# sensor_pcb_4.net
KiCad netlist of a schematic drawn in EAGLE
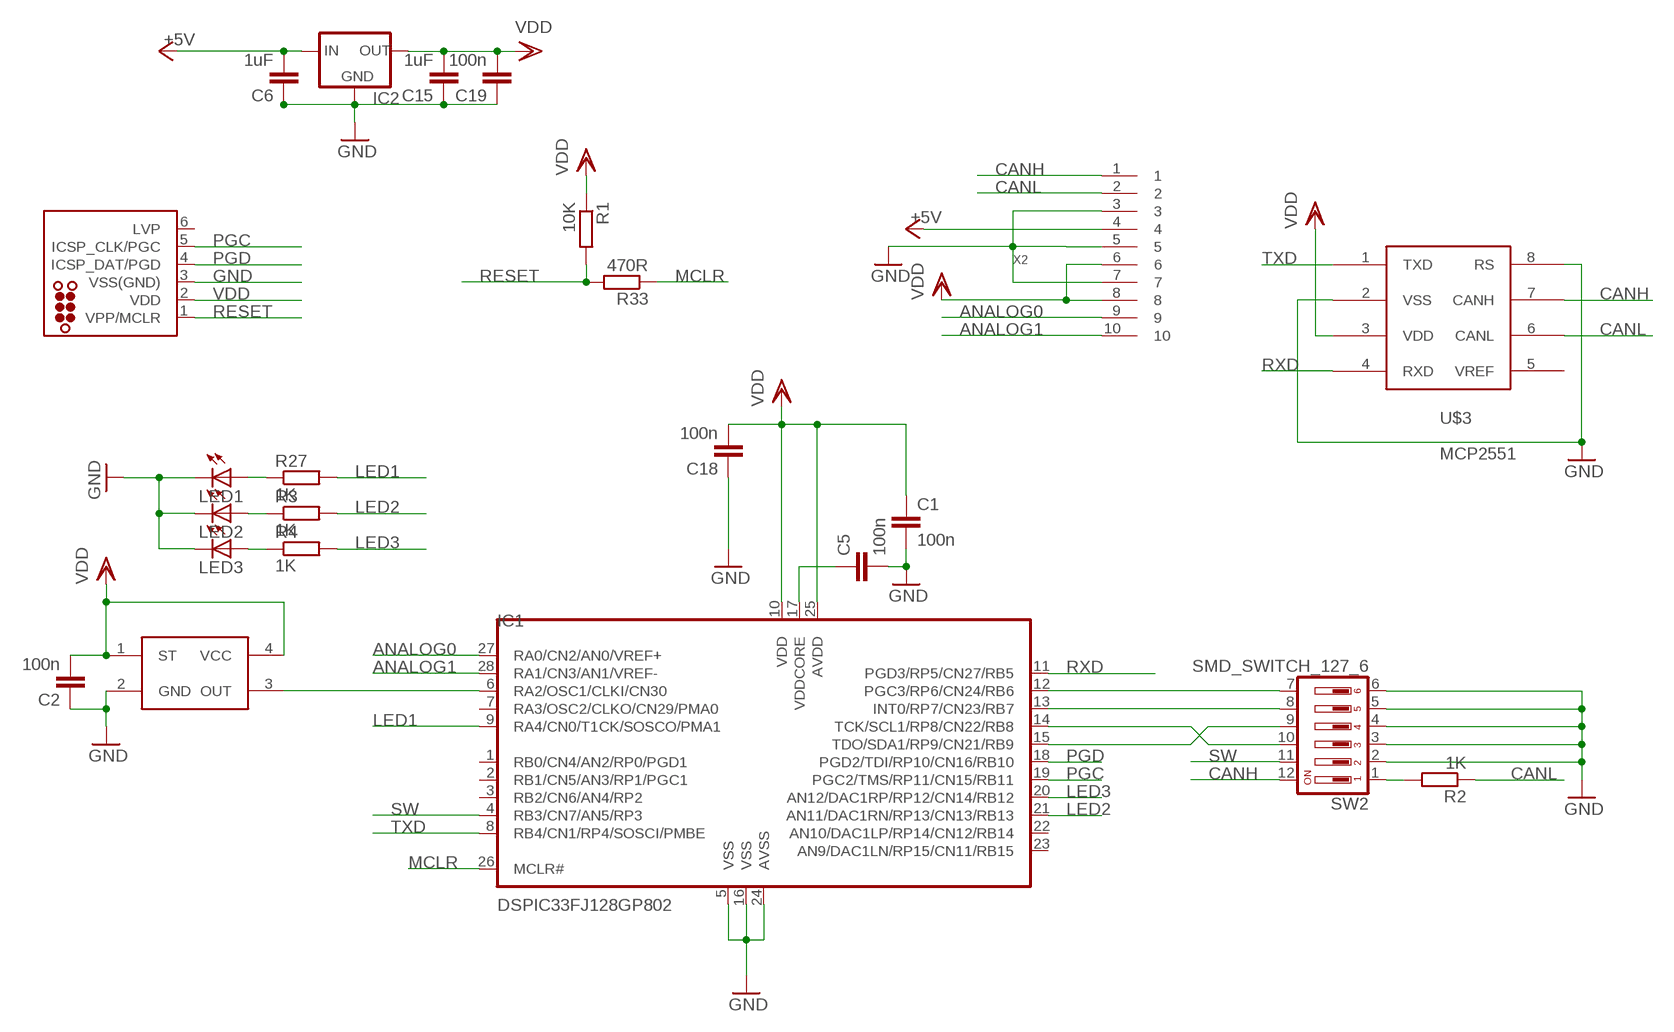
[diagram p0: schematic, sheet 1]

(export (version "E")
  (design (tool "Eeschema 10.0.6"))
  (components
    (comp (ref "C1")
      (value "100n")
      (footprint "eagle-import:C0402K")
      (libsource (lib "eagle-import") (part "C-EUC0402K"))
    )
    (comp (ref "C2")
      (value "100n")
      (footprint "eagle-import:C0402K")
      (libsource (lib "eagle-import") (part "C-EUC0402K"))
    )
    (comp (ref "C5")
      (value "100n")
      (footprint "eagle-import:C0402K")
      (libsource (lib "eagle-import") (part "C-EUC0402K"))
    )
    (comp (ref "C6")
      (value "1uF")
      (footprint "eagle-import:C0402K")
      (libsource (lib "eagle-import") (part "C-EUC0402K"))
    )
    (comp (ref "C15")
      (value "1uF")
      (footprint "eagle-import:C0402K")
      (libsource (lib "eagle-import") (part "C-EUC0402K"))
    )
    (comp (ref "C18")
      (value "100n")
      (footprint "eagle-import:C0402K")
      (libsource (lib "eagle-import") (part "C-EUC0402K"))
    )
    (comp (ref "C19")
      (value "100n")
      (footprint "eagle-import:C0402K")
      (libsource (lib "eagle-import") (part "C-EUC0402K"))
    )
    (comp (ref "IC1")
      (value "DSPIC33FJ128GP802")
      (footprint "eagle-import:QFN-S28-6X6")
      (libsource (lib "eagle-import") (part "DSPIC33FJ128GP802"))
    )
    (comp (ref "IC2")
      (value "XC63FPM")
      (footprint "eagle-import:SOT23")
      (libsource (lib "eagle-import") (part "XC63FPM"))
    )
    (comp (ref "J1")
      (value "TC2030-MCP-NL")
      (footprint "eagle-import:TC2030-MCP-NL")
      (libsource (lib "eagle-import") (part "TC2030-MCP-NL"))
    )
    (comp (ref "LED1")
      (value "LEDCHIPLED_0603")
      (footprint "eagle-import:CHIPLED_0603")
      (libsource (lib "eagle-import") (part "LEDCHIPLED_0603"))
    )
    (comp (ref "LED2")
      (value "LEDCHIPLED_0603")
      (footprint "eagle-import:CHIPLED_0603")
      (libsource (lib "eagle-import") (part "LEDCHIPLED_0603"))
    )
    (comp (ref "LED3")
      (value "LEDCHIPLED_0603")
      (footprint "eagle-import:CHIPLED_0603")
      (libsource (lib "eagle-import") (part "LEDCHIPLED_0603"))
    )
    (comp (ref "R1")
      (value "10K")
      (footprint "eagle-import:R0402")
      (libsource (lib "eagle-import") (part "R-EU_R0402"))
    )
    (comp (ref "R2")
      (value "1K")
      (footprint "eagle-import:R0402")
      (libsource (lib "eagle-import") (part "R-EU_R0402"))
    )
    (comp (ref "R3")
      (value "1K")
      (footprint "eagle-import:R0402")
      (libsource (lib "eagle-import") (part "R-EU_R0402"))
    )
    (comp (ref "R4")
      (value "1K")
      (footprint "eagle-import:R0402")
      (libsource (lib "eagle-import") (part "R-EU_R0402"))
    )
    (comp (ref "R27")
      (value "1K")
      (footprint "eagle-import:R0402")
      (libsource (lib "eagle-import") (part "R-EU_R0402"))
    )
    (comp (ref "R33")
      (value "470R")
      (footprint "eagle-import:R0402")
      (libsource (lib "eagle-import") (part "R-EU_R0402"))
    )
    (comp (ref "SW2")
      (value "SMD_SWITCH_127_6")
      (footprint "eagle-import:SMD_SWITCH_127_6")
      (libsource (lib "eagle-import") (part "SMD_SWITCH_127_6"))
    )
    (comp (ref "U$1")
      (value "SG-310")
      (footprint "eagle-import:SG-310")
      (libsource (lib "eagle-import") (part "SG-310"))
    )
    (comp (ref "U$3")
      (value "MCP2551")
      (footprint "eagle-import:999")
      (libsource (lib "eagle-import") (part "MCP2551"))
    )
    (comp (ref "X2")
      (value "10PINJAS")
      (footprint "eagle-import:10PIN0.1")
      (libsource (lib "eagle-import") (part "10PINJAS"))
    )
  )
  (nets
    (net (code "1") (name "+5V") (class "Default")
      (node (ref "C6") (pin "2") (pinfunction "2_2") (pintype "passive"))
      (node (ref "IC2") (pin "3") (pinfunction "IN_3") (pintype "input"))
      (node (ref "X2") (pin "4") (pinfunction "4_4") (pintype "bidirectional"))
    )
    (net (code "2") (name "/ANALOG0") (class "Default")
      (node (ref "IC1") (pin "27") (pinfunction "RA0/CN2/AN0/VREF+_27") (pintype "bidirectional"))
      (node (ref "X2") (pin "9") (pinfunction "9_9") (pintype "bidirectional"))
    )
    (net (code "3") (name "/ANALOG1") (class "Default")
      (node (ref "IC1") (pin "28") (pinfunction "RA1/CN3/AN1/VREF-_28") (pintype "bidirectional"))
      (node (ref "X2") (pin "10") (pinfunction "10_10") (pintype "bidirectional"))
    )
    (net (code "4") (name "/CANH") (class "Default")
      (node (ref "SW2") (pin "12") (pinfunction "12_12") (pintype "passive"))
      (node (ref "U$3") (pin "7") (pinfunction "CANH_7") (pintype "bidirectional"))
      (node (ref "X2") (pin "1") (pinfunction "1_1") (pintype "bidirectional"))
    )
    (net (code "5") (name "/CANL") (class "Default")
      (node (ref "R2") (pin "1") (pinfunction "1_1") (pintype "passive"))
      (node (ref "U$3") (pin "6") (pinfunction "CANL_6") (pintype "bidirectional"))
      (node (ref "X2") (pin "2") (pinfunction "2_2") (pintype "bidirectional"))
    )
    (net (code "6") (name "/LED1") (class "Default")
      (node (ref "IC1") (pin "9") (pinfunction "RA4/CN0/T1CK/SOSCO/PMA1_9") (pintype "bidirectional"))
      (node (ref "R27") (pin "2") (pinfunction "2_2") (pintype "passive"))
    )
    (net (code "7") (name "/LED2") (class "Default")
      (node (ref "IC1") (pin "21") (pinfunction "AN11/DAC1RN/RP13/CN13/RB13_21") (pintype "bidirectional"))
      (node (ref "R3") (pin "2") (pinfunction "2_2") (pintype "passive"))
    )
    (net (code "8") (name "/LED3") (class "Default")
      (node (ref "IC1") (pin "20") (pinfunction "AN12/DAC1RP/RP12/CN14/RB12_20") (pintype "bidirectional"))
      (node (ref "R4") (pin "2") (pinfunction "2_2") (pintype "passive"))
    )
    (net (code "9") (name "/MCLR") (class "Default")
      (node (ref "IC1") (pin "26") (pinfunction "MCLR#_26") (pintype "input"))
      (node (ref "R33") (pin "1") (pinfunction "1_1") (pintype "passive"))
    )
    (net (code "10") (name "/PGC") (class "Default")
      (node (ref "IC1") (pin "19") (pinfunction "PGC2/TMS/RP11/CN15/RB11_19") (pintype "bidirectional"))
      (node (ref "J1") (pin "5") (pinfunction "ICSP_CLK/PGC_5") (pintype "output"))
    )
    (net (code "11") (name "/PGD") (class "Default")
      (node (ref "IC1") (pin "18") (pinfunction "PGD2/TDI/RP10/CN16/RB10_18") (pintype "bidirectional"))
      (node (ref "J1") (pin "4") (pinfunction "ICSP_DAT/PGD_4") (pintype "bidirectional"))
    )
    (net (code "12") (name "/RESET") (class "Default")
      (node (ref "J1") (pin "1") (pinfunction "VPP/MCLR_1") (pintype "passive"))
      (node (ref "R1") (pin "2") (pinfunction "2_2") (pintype "passive"))
      (node (ref "R33") (pin "2") (pinfunction "2_2") (pintype "passive"))
    )
    (net (code "13") (name "/RXD") (class "Default")
      (node (ref "IC1") (pin "11") (pinfunction "PGD3/RP5/CN27/RB5_11") (pintype "bidirectional"))
      (node (ref "U$3") (pin "4") (pinfunction "RXD_4") (pintype "bidirectional"))
    )
    (net (code "14") (name "/SW") (class "Default")
      (node (ref "IC1") (pin "4") (pinfunction "RB3/CN7/AN5/RP3_4") (pintype "bidirectional"))
      (node (ref "SW2") (pin "11") (pinfunction "11_11") (pintype "passive"))
    )
    (net (code "15") (name "/TXD") (class "Default")
      (node (ref "IC1") (pin "8") (pinfunction "RB4/CN1/RP4/SOSCI/PMBE_8") (pintype "bidirectional"))
      (node (ref "U$3") (pin "1") (pinfunction "TXD_1") (pintype "bidirectional"))
    )
    (net (code "16") (name "GND") (class "Default")
      (node (ref "C1") (pin "2") (pinfunction "2_2") (pintype "passive"))
      (node (ref "C15") (pin "1") (pinfunction "1_1") (pintype "passive"))
      (node (ref "C18") (pin "1") (pinfunction "1_1") (pintype "passive"))
      (node (ref "C19") (pin "1") (pinfunction "1_1") (pintype "passive"))
      (node (ref "C2") (pin "1") (pinfunction "1_1") (pintype "passive"))
      (node (ref "C5") (pin "2") (pinfunction "2_2") (pintype "passive"))
      (node (ref "C6") (pin "1") (pinfunction "1_1") (pintype "passive"))
      (node (ref "IC1") (pin "16") (pinfunction "VSS_16") (pintype "power_in"))
      (node (ref "IC1") (pin "24") (pinfunction "AVSS_24") (pintype "power_in"))
      (node (ref "IC1") (pin "5") (pinfunction "VSS_5") (pintype "power_in"))
      (node (ref "IC2") (pin "1") (pinfunction "GND_1") (pintype "input"))
      (node (ref "J1") (pin "3") (pinfunction "VSS(GND)_3") (pintype "power_in"))
      (node (ref "LED1") (pin "C") (pinfunction "C_C") (pintype "passive"))
      (node (ref "LED2") (pin "C") (pinfunction "C_C") (pintype "passive"))
      (node (ref "LED3") (pin "C") (pinfunction "C_C") (pintype "passive"))
      (node (ref "SW2") (pin "2") (pinfunction "2_2") (pintype "passive"))
      (node (ref "SW2") (pin "3") (pinfunction "3_3") (pintype "passive"))
      (node (ref "SW2") (pin "4") (pinfunction "4_4") (pintype "passive"))
      (node (ref "SW2") (pin "5") (pinfunction "5_5") (pintype "passive"))
      (node (ref "SW2") (pin "6") (pinfunction "6_6") (pintype "passive"))
      (node (ref "U$1") (pin "2") (pinfunction "GND_2") (pintype "bidirectional"))
      (node (ref "U$3") (pin "2") (pinfunction "VSS_2") (pintype "power_in"))
      (node (ref "U$3") (pin "8") (pinfunction "RS_8") (pintype "bidirectional"))
      (node (ref "X2") (pin "3") (pinfunction "3_3") (pintype "bidirectional"))
      (node (ref "X2") (pin "5") (pinfunction "5_5") (pintype "bidirectional"))
      (node (ref "X2") (pin "7") (pinfunction "7_7") (pintype "bidirectional"))
    )
    (net (code "17") (name "Net-(IC1-INT0{slash}RP7{slash}CN23{slash}RB7)") (class "Default")
      (node (ref "IC1") (pin "13") (pinfunction "INT0/RP7/CN23/RB7_13") (pintype "bidirectional"))
      (node (ref "SW2") (pin "8") (pinfunction "8_8") (pintype "passive"))
    )
    (net (code "18") (name "Net-(IC1-PGC3{slash}RP6{slash}CN24{slash}RB6)") (class "Default")
      (node (ref "IC1") (pin "12") (pinfunction "PGC3/RP6/CN24/RB6_12") (pintype "bidirectional"))
      (node (ref "SW2") (pin "7") (pinfunction "7_7") (pintype "passive"))
    )
    (net (code "19") (name "Net-(IC1-RA2{slash}OSC1{slash}CLKI{slash}CN30)") (class "Default")
      (node (ref "IC1") (pin "6") (pinfunction "RA2/OSC1/CLKI/CN30_6") (pintype "bidirectional"))
      (node (ref "U$1") (pin "3") (pinfunction "OUT_3") (pintype "bidirectional"))
    )
    (net (code "20") (name "Net-(IC1-TCK{slash}SCL1{slash}RP8{slash}CN22{slash}RB8)") (class "Default")
      (node (ref "IC1") (pin "14") (pinfunction "TCK/SCL1/RP8/CN22/RB8_14") (pintype "bidirectional"))
      (node (ref "SW2") (pin "10") (pinfunction "10_10") (pintype "passive"))
    )
    (net (code "21") (name "Net-(IC1-TDO{slash}SDA1{slash}RP9{slash}CN21{slash}RB9)") (class "Default")
      (node (ref "IC1") (pin "15") (pinfunction "TDO/SDA1/RP9/CN21/RB9_15") (pintype "bidirectional"))
      (node (ref "SW2") (pin "9") (pinfunction "9_9") (pintype "passive"))
    )
    (net (code "22") (name "Net-(IC1-VDDCORE)") (class "Default")
      (node (ref "C5") (pin "1") (pinfunction "1_1") (pintype "passive"))
      (node (ref "IC1") (pin "17") (pinfunction "VDDCORE_17") (pintype "power_in"))
    )
    (net (code "23") (name "Net-(LED1-PadA)") (class "Default")
      (node (ref "LED1") (pin "A") (pinfunction "A_A") (pintype "passive"))
      (node (ref "R27") (pin "1") (pinfunction "1_1") (pintype "passive"))
    )
    (net (code "24") (name "Net-(LED2-PadA)") (class "Default")
      (node (ref "LED2") (pin "A") (pinfunction "A_A") (pintype "passive"))
      (node (ref "R3") (pin "1") (pinfunction "1_1") (pintype "passive"))
    )
    (net (code "25") (name "Net-(LED3-PadA)") (class "Default")
      (node (ref "LED3") (pin "A") (pinfunction "A_A") (pintype "passive"))
      (node (ref "R4") (pin "1") (pinfunction "1_1") (pintype "passive"))
    )
    (net (code "26") (name "Net-(R2-Pad2)") (class "Default")
      (node (ref "R2") (pin "2") (pinfunction "2_2") (pintype "passive"))
      (node (ref "SW2") (pin "1") (pinfunction "1_1") (pintype "passive"))
    )
    (net (code "27") (name "VDD") (class "Default")
      (node (ref "C1") (pin "1") (pinfunction "1_1") (pintype "passive"))
      (node (ref "C15") (pin "2") (pinfunction "2_2") (pintype "passive"))
      (node (ref "C18") (pin "2") (pinfunction "2_2") (pintype "passive"))
      (node (ref "C19") (pin "2") (pinfunction "2_2") (pintype "passive"))
      (node (ref "C2") (pin "2") (pinfunction "2_2") (pintype "passive"))
      (node (ref "IC1") (pin "10") (pinfunction "VDD_10") (pintype "power_in"))
      (node (ref "IC1") (pin "25") (pinfunction "AVDD_25") (pintype "power_in"))
      (node (ref "IC2") (pin "2") (pinfunction "OUT_2") (pintype "passive"))
      (node (ref "J1") (pin "2") (pinfunction "VDD_2") (pintype "power_in"))
      (node (ref "R1") (pin "1") (pinfunction "1_1") (pintype "passive"))
      (node (ref "U$1") (pin "1") (pinfunction "ST_1") (pintype "bidirectional"))
      (node (ref "U$1") (pin "4") (pinfunction "VCC_4") (pintype "bidirectional"))
      (node (ref "U$3") (pin "3") (pinfunction "VDD_3") (pintype "power_in"))
      (node (ref "X2") (pin "6") (pinfunction "6_6") (pintype "bidirectional"))
      (node (ref "X2") (pin "8") (pinfunction "8_8") (pintype "bidirectional"))
    )
    (net (code "28") (name "unconnected-(IC1-AN9{slash}DAC1LN{slash}RP15{slash}CN11{slash}RB15-Pad23)") (class "Default")
      (node (ref "IC1") (pin "23") (pinfunction "AN9/DAC1LN/RP15/CN11/RB15_23") (pintype "bidirectional"))
    )
    (net (code "29") (name "unconnected-(IC1-AN10{slash}DAC1LP{slash}RP14{slash}CN12{slash}RB14-Pad22)") (class "Default")
      (node (ref "IC1") (pin "22") (pinfunction "AN10/DAC1LP/RP14/CN12/RB14_22") (pintype "bidirectional"))
    )
    (net (code "30") (name "unconnected-(IC1-RA3{slash}OSC2{slash}CLKO{slash}CN29{slash}PMA0-Pad7)") (class "Default")
      (node (ref "IC1") (pin "7") (pinfunction "RA3/OSC2/CLKO/CN29/PMA0_7") (pintype "bidirectional"))
    )
    (net (code "31") (name "unconnected-(IC1-RB0{slash}CN4{slash}AN2{slash}RP0{slash}PGD1-Pad1)") (class "Default")
      (node (ref "IC1") (pin "1") (pinfunction "RB0/CN4/AN2/RP0/PGD1_1") (pintype "bidirectional"))
    )
    (net (code "32") (name "unconnected-(IC1-RB1{slash}CN5{slash}AN3{slash}RP1{slash}PGC1-Pad2)") (class "Default")
      (node (ref "IC1") (pin "2") (pinfunction "RB1/CN5/AN3/RP1/PGC1_2") (pintype "bidirectional"))
    )
    (net (code "33") (name "unconnected-(IC1-RB2{slash}CN6{slash}AN4{slash}RP2-Pad3)") (class "Default")
      (node (ref "IC1") (pin "3") (pinfunction "RB2/CN6/AN4/RP2_3") (pintype "bidirectional"))
    )
    (net (code "34") (name "unconnected-(J1-LVP-Pad6)") (class "Default")
      (node (ref "J1") (pin "6") (pinfunction "LVP_6") (pintype "bidirectional"))
    )
    (net (code "35") (name "unconnected-(U$3-VREF-Pad5)") (class "Default")
      (node (ref "U$3") (pin "5") (pinfunction "VREF_5") (pintype "bidirectional"))
    )
  )
)
